# MotherBoard.net
KiCad netlist of a schematic drawn in EasyEDA Pro
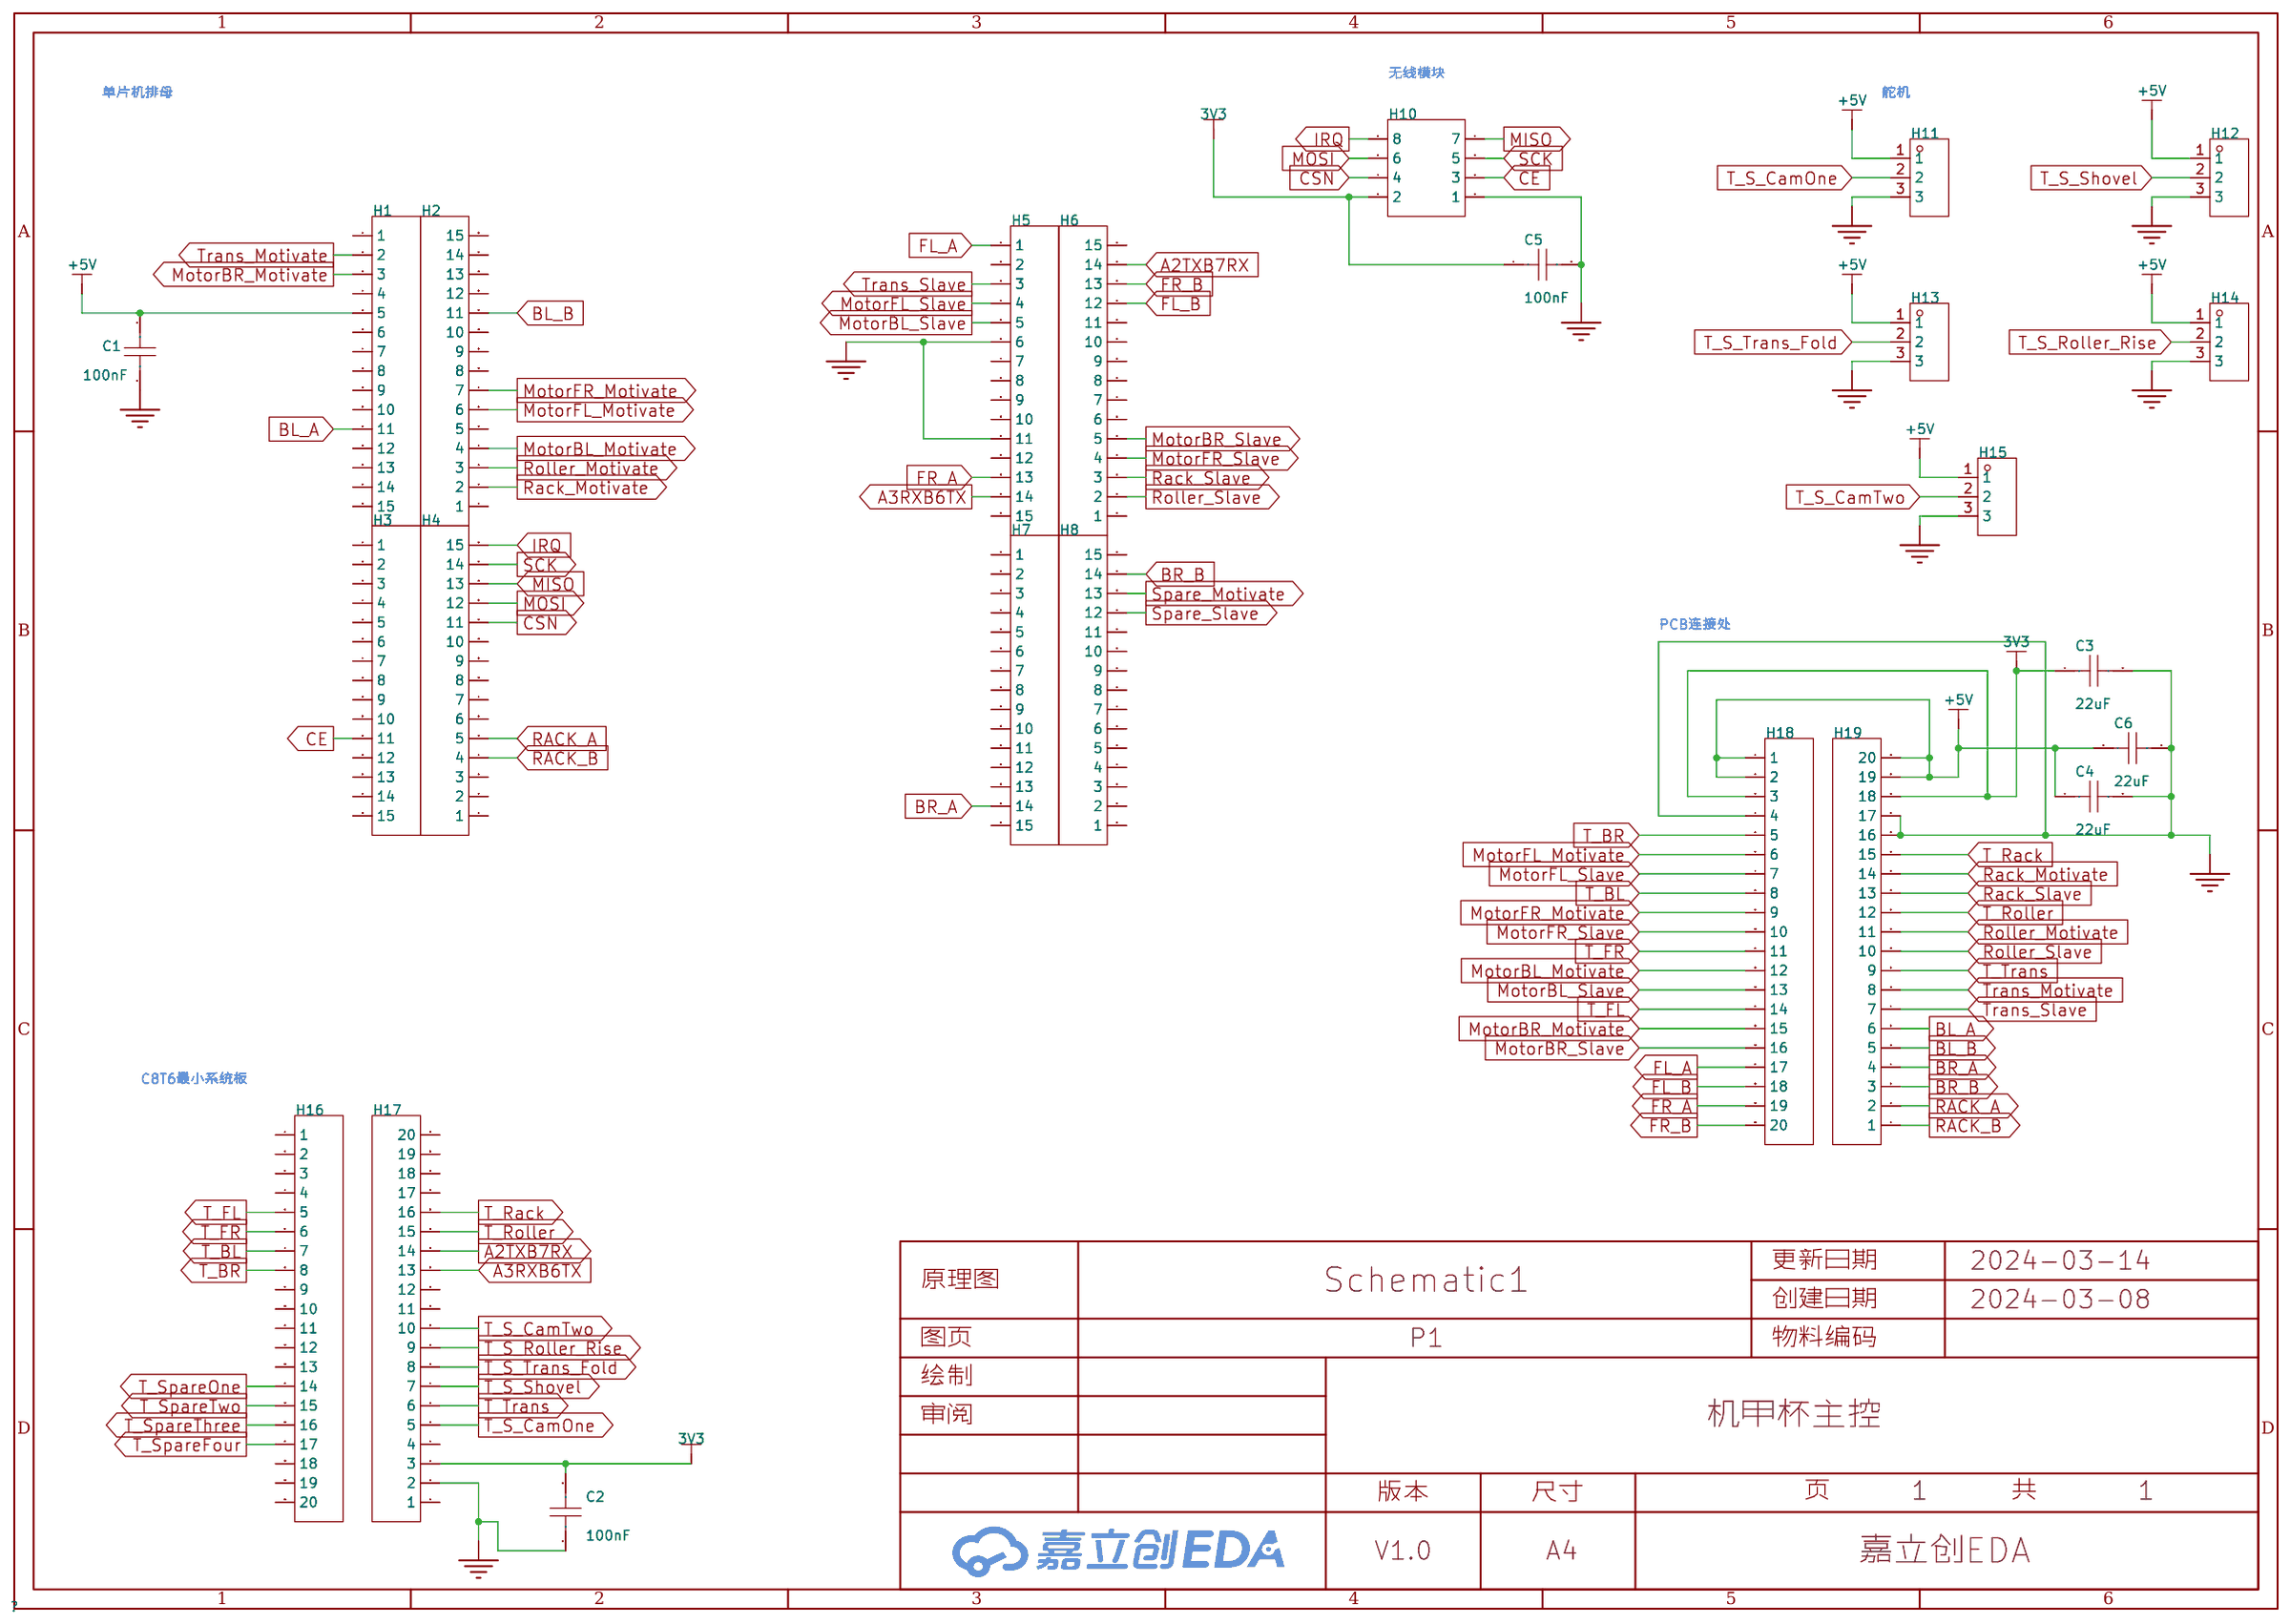
[diagram p0: schematic sheet]

(export (version "E")
  (design (tool "Eeschema 10.0.6"))
  (components
    (comp (ref "C1")
      (value "100nF")
      (footprint "easyedapro:C0603")
      (libsource (lib "easyedapro") (part "CapAcitance"))
    )
    (comp (ref "C2")
      (value "100nF")
      (footprint "easyedapro:C0603")
      (libsource (lib "easyedapro") (part "CapAcitance"))
    )
    (comp (ref "C3")
      (value "22uF")
      (footprint "easyedapro:C0603")
      (libsource (lib "easyedapro") (part "CapAcitance"))
    )
    (comp (ref "C4")
      (value "22uF")
      (footprint "easyedapro:C0603")
      (libsource (lib "easyedapro") (part "CapAcitance"))
    )
    (comp (ref "C5")
      (value "100nF")
      (footprint "easyedapro:C0603")
      (libsource (lib "easyedapro") (part "CapAcitance"))
    )
    (comp (ref "C6")
      (value "22uF")
      (footprint "easyedapro:C0603")
      (libsource (lib "easyedapro") (part "CapAcitance"))
    )
    (comp (ref "H1")
      (value "~")
      (footprint "easyedapro:HDR-TH_15P-P2.54-V-F-1")
      (libsource (lib "easyedapro") (part "HDR-F_2.54_1x15P"))
    )
    (comp (ref "H2")
      (value "~")
      (footprint "easyedapro:HDR-TH_15P-P2.54-V-F-1")
      (libsource (lib "easyedapro") (part "HDR-F_2.54_1x15P"))
    )
    (comp (ref "H3")
      (value "~")
      (footprint "easyedapro:HDR-TH_15P-P2.54-V-F-1")
      (libsource (lib "easyedapro") (part "HDR-F_2.54_1x15P"))
    )
    (comp (ref "H4")
      (value "~")
      (footprint "easyedapro:HDR-TH_15P-P2.54-V-F-1")
      (libsource (lib "easyedapro") (part "HDR-F_2.54_1x15P"))
    )
    (comp (ref "H5")
      (value "~")
      (footprint "easyedapro:HDR-TH_15P-P2.54-V-F-1")
      (libsource (lib "easyedapro") (part "HDR-F_2.54_1x15P"))
    )
    (comp (ref "H6")
      (value "~")
      (footprint "easyedapro:HDR-TH_15P-P2.54-V-F-1")
      (libsource (lib "easyedapro") (part "HDR-F_2.54_1x15P"))
    )
    (comp (ref "H7")
      (value "~")
      (footprint "easyedapro:HDR-TH_15P-P2.54-V-F-1")
      (libsource (lib "easyedapro") (part "HDR-F_2.54_1x15P"))
    )
    (comp (ref "H8")
      (value "~")
      (footprint "easyedapro:HDR-TH_15P-P2.54-V-F-1")
      (libsource (lib "easyedapro") (part "HDR-F_2.54_1x15P"))
    )
    (comp (ref "H10")
      (value "~")
      (footprint "easyedapro:HDR-TH_8P-P2.54-V-F-R2-C4-S2.54-1")
      (libsource (lib "easyedapro") (part "HDR-F-2.54_2x4"))
    )
    (comp (ref "H11")
      (value "~")
      (footprint "easyedapro:HDR-TH_3P-P2.54-V-M")
      (libsource (lib "easyedapro") (part "PZ254V-11-03P_C2937625"))
    )
    (comp (ref "H12")
      (value "~")
      (footprint "easyedapro:HDR-TH_3P-P2.54-V-M")
      (libsource (lib "easyedapro") (part "PZ254V-11-03P_C2937625"))
    )
    (comp (ref "H13")
      (value "~")
      (footprint "easyedapro:HDR-TH_3P-P2.54-V-M")
      (libsource (lib "easyedapro") (part "PZ254V-11-03P_C2937625"))
    )
    (comp (ref "H14")
      (value "~")
      (footprint "easyedapro:HDR-TH_3P-P2.54-V-M")
      (libsource (lib "easyedapro") (part "PZ254V-11-03P_C2937625"))
    )
    (comp (ref "H15")
      (value "~")
      (footprint "easyedapro:HDR-TH_3P-P2.54-V-M")
      (libsource (lib "easyedapro") (part "PZ254V-11-03P_C2937625"))
    )
    (comp (ref "H16")
      (value "~")
      (footprint "easyedapro:HDR-TH_20P-P2.54-V-F")
      (libsource (lib "easyedapro") (part "HDR-F_2.54_1x20P"))
    )
    (comp (ref "H17")
      (value "~")
      (footprint "easyedapro:HDR-TH_20P-P2.54-V-F")
      (libsource (lib "easyedapro") (part "HDR-F_2.54_1x20P"))
    )
    (comp (ref "H18")
      (value "~")
      (footprint "easyedapro:HDR-TH_20P-P2.54-V-F")
      (libsource (lib "easyedapro") (part "HDR-F_2.54_1x20P"))
    )
    (comp (ref "H19")
      (value "~")
      (footprint "easyedapro:HDR-TH_20P-P2.54-V-F")
      (libsource (lib "easyedapro") (part "HDR-F_2.54_1x20P"))
    )
  )
  (nets
    (net (code "1") (name "+5V") (class "Default")
      (node (ref "C1") (pin "2") (pinfunction "2_2") (pintype "input"))
      (node (ref "C4") (pin "1") (pinfunction "1_1") (pintype "input"))
      (node (ref "C6") (pin "2") (pinfunction "2_2") (pintype "input"))
      (node (ref "H1") (pin "5") (pinfunction "5_5") (pintype "input"))
      (node (ref "H11") (pin "1") (pinfunction "1_1") (pintype "input"))
      (node (ref "H12") (pin "1") (pinfunction "1_1") (pintype "input"))
      (node (ref "H13") (pin "1") (pinfunction "1_1") (pintype "input"))
      (node (ref "H14") (pin "1") (pinfunction "1_1") (pintype "input"))
      (node (ref "H15") (pin "1") (pinfunction "1_1") (pintype "input"))
      (node (ref "H18") (pin "1") (pinfunction "1_1") (pintype "input"))
      (node (ref "H18") (pin "2") (pinfunction "2_2") (pintype "input"))
      (node (ref "H19") (pin "19") (pinfunction "19_19") (pintype "input"))
      (node (ref "H19") (pin "20") (pinfunction "20_20") (pintype "input"))
    )
    (net (code "2") (name "3V3") (class "Default")
      (node (ref "C2") (pin "2") (pinfunction "2_2") (pintype "input"))
      (node (ref "C3") (pin "1") (pinfunction "1_1") (pintype "input"))
      (node (ref "C5") (pin "1") (pinfunction "1_1") (pintype "input"))
      (node (ref "H10") (pin "2") (pinfunction "2_2") (pintype "input"))
      (node (ref "H17") (pin "3") (pinfunction "3_3") (pintype "input"))
      (node (ref "H18") (pin "3") (pinfunction "3_3") (pintype "input"))
      (node (ref "H19") (pin "18") (pinfunction "18_18") (pintype "input"))
    )
    (net (code "3") (name "A2TXB7RX") (class "Default")
      (node (ref "H17") (pin "14") (pinfunction "14_14") (pintype "input"))
      (node (ref "H6") (pin "14") (pinfunction "14_14") (pintype "input"))
    )
    (net (code "4") (name "A3RXB6TX") (class "Default")
      (node (ref "H17") (pin "13") (pinfunction "13_13") (pintype "input"))
      (node (ref "H5") (pin "14") (pinfunction "14_14") (pintype "input"))
    )
    (net (code "5") (name "BL_A") (class "Default")
      (node (ref "H1") (pin "11") (pinfunction "11_11") (pintype "input"))
      (node (ref "H19") (pin "6") (pinfunction "6_6") (pintype "input"))
    )
    (net (code "6") (name "BL_B") (class "Default")
      (node (ref "H19") (pin "5") (pinfunction "5_5") (pintype "input"))
      (node (ref "H2") (pin "11") (pinfunction "11_11") (pintype "input"))
    )
    (net (code "7") (name "BR_A") (class "Default")
      (node (ref "H19") (pin "4") (pinfunction "4_4") (pintype "input"))
      (node (ref "H7") (pin "14") (pinfunction "14_14") (pintype "input"))
    )
    (net (code "8") (name "BR_B") (class "Default")
      (node (ref "H19") (pin "3") (pinfunction "3_3") (pintype "input"))
      (node (ref "H8") (pin "14") (pinfunction "14_14") (pintype "input"))
    )
    (net (code "9") (name "CE") (class "Default")
      (node (ref "H10") (pin "3") (pinfunction "3_3") (pintype "input"))
      (node (ref "H3") (pin "11") (pinfunction "11_11") (pintype "input"))
    )
    (net (code "10") (name "CSN") (class "Default")
      (node (ref "H10") (pin "4") (pinfunction "4_4") (pintype "input"))
      (node (ref "H4") (pin "11") (pinfunction "11_11") (pintype "input"))
    )
    (net (code "11") (name "FL_A") (class "Default")
      (node (ref "H18") (pin "17") (pinfunction "17_17") (pintype "input"))
      (node (ref "H5") (pin "1") (pinfunction "1_1") (pintype "input"))
    )
    (net (code "12") (name "FL_B") (class "Default")
      (node (ref "H18") (pin "18") (pinfunction "18_18") (pintype "input"))
      (node (ref "H6") (pin "12") (pinfunction "12_12") (pintype "input"))
    )
    (net (code "13") (name "FR_A") (class "Default")
      (node (ref "H18") (pin "19") (pinfunction "19_19") (pintype "input"))
      (node (ref "H5") (pin "13") (pinfunction "13_13") (pintype "input"))
    )
    (net (code "14") (name "FR_B") (class "Default")
      (node (ref "H18") (pin "20") (pinfunction "20_20") (pintype "input"))
      (node (ref "H6") (pin "13") (pinfunction "13_13") (pintype "input"))
    )
    (net (code "15") (name "GND") (class "Default")
      (node (ref "C1") (pin "1") (pinfunction "1_1") (pintype "input"))
      (node (ref "C2") (pin "1") (pinfunction "1_1") (pintype "input"))
      (node (ref "C3") (pin "2") (pinfunction "2_2") (pintype "input"))
      (node (ref "C4") (pin "2") (pinfunction "2_2") (pintype "input"))
      (node (ref "C5") (pin "2") (pinfunction "2_2") (pintype "input"))
      (node (ref "C6") (pin "1") (pinfunction "1_1") (pintype "input"))
      (node (ref "H10") (pin "1") (pinfunction "1_1") (pintype "input"))
      (node (ref "H11") (pin "3") (pinfunction "3_3") (pintype "input"))
      (node (ref "H12") (pin "3") (pinfunction "3_3") (pintype "input"))
      (node (ref "H13") (pin "3") (pinfunction "3_3") (pintype "input"))
      (node (ref "H14") (pin "3") (pinfunction "3_3") (pintype "input"))
      (node (ref "H15") (pin "3") (pinfunction "3_3") (pintype "input"))
      (node (ref "H17") (pin "2") (pinfunction "2_2") (pintype "input"))
      (node (ref "H18") (pin "4") (pinfunction "4_4") (pintype "input"))
      (node (ref "H19") (pin "16") (pinfunction "16_16") (pintype "input"))
      (node (ref "H19") (pin "17") (pinfunction "17_17") (pintype "input"))
      (node (ref "H5") (pin "11") (pinfunction "11_11") (pintype "input"))
      (node (ref "H5") (pin "6") (pinfunction "6_6") (pintype "input"))
    )
    (net (code "16") (name "IRQ") (class "Default")
      (node (ref "H10") (pin "8") (pinfunction "8_8") (pintype "input"))
      (node (ref "H4") (pin "15") (pinfunction "15_15") (pintype "input"))
    )
    (net (code "17") (name "MISO") (class "Default")
      (node (ref "H10") (pin "7") (pinfunction "7_7") (pintype "input"))
      (node (ref "H4") (pin "13") (pinfunction "13_13") (pintype "input"))
    )
    (net (code "18") (name "MOSI") (class "Default")
      (node (ref "H10") (pin "6") (pinfunction "6_6") (pintype "input"))
      (node (ref "H4") (pin "12") (pinfunction "12_12") (pintype "input"))
    )
    (net (code "19") (name "MotorBL_Motivate") (class "Default")
      (node (ref "H18") (pin "12") (pinfunction "12_12") (pintype "input"))
      (node (ref "H2") (pin "4") (pinfunction "4_4") (pintype "input"))
    )
    (net (code "20") (name "MotorBL_Slave") (class "Default")
      (node (ref "H18") (pin "13") (pinfunction "13_13") (pintype "input"))
      (node (ref "H5") (pin "5") (pinfunction "5_5") (pintype "input"))
    )
    (net (code "21") (name "MotorBR_Motivate") (class "Default")
      (node (ref "H1") (pin "3") (pinfunction "3_3") (pintype "input"))
      (node (ref "H18") (pin "15") (pinfunction "15_15") (pintype "input"))
    )
    (net (code "22") (name "MotorBR_Slave") (class "Default")
      (node (ref "H18") (pin "16") (pinfunction "16_16") (pintype "input"))
      (node (ref "H6") (pin "5") (pinfunction "5_5") (pintype "input"))
    )
    (net (code "23") (name "MotorFL_Motivate") (class "Default")
      (node (ref "H18") (pin "6") (pinfunction "6_6") (pintype "input"))
      (node (ref "H2") (pin "6") (pinfunction "6_6") (pintype "input"))
    )
    (net (code "24") (name "MotorFL_Slave") (class "Default")
      (node (ref "H18") (pin "7") (pinfunction "7_7") (pintype "input"))
      (node (ref "H5") (pin "4") (pinfunction "4_4") (pintype "input"))
    )
    (net (code "25") (name "MotorFR_Motivate") (class "Default")
      (node (ref "H18") (pin "9") (pinfunction "9_9") (pintype "input"))
      (node (ref "H2") (pin "7") (pinfunction "7_7") (pintype "input"))
    )
    (net (code "26") (name "MotorFR_Slave") (class "Default")
      (node (ref "H18") (pin "10") (pinfunction "10_10") (pintype "input"))
      (node (ref "H6") (pin "4") (pinfunction "4_4") (pintype "input"))
    )
    (net (code "27") (name "RACK_A") (class "Default")
      (node (ref "H19") (pin "2") (pinfunction "2_2") (pintype "input"))
      (node (ref "H4") (pin "5") (pinfunction "5_5") (pintype "input"))
    )
    (net (code "28") (name "RACK_B") (class "Default")
      (node (ref "H19") (pin "1") (pinfunction "1_1") (pintype "input"))
      (node (ref "H4") (pin "4") (pinfunction "4_4") (pintype "input"))
    )
    (net (code "29") (name "Rack_Motivate") (class "Default")
      (node (ref "H19") (pin "14") (pinfunction "14_14") (pintype "input"))
      (node (ref "H2") (pin "2") (pinfunction "2_2") (pintype "input"))
    )
    (net (code "30") (name "Rack_Slave") (class "Default")
      (node (ref "H19") (pin "13") (pinfunction "13_13") (pintype "input"))
      (node (ref "H6") (pin "3") (pinfunction "3_3") (pintype "input"))
    )
    (net (code "31") (name "Roller_Motivate") (class "Default")
      (node (ref "H19") (pin "11") (pinfunction "11_11") (pintype "input"))
      (node (ref "H2") (pin "3") (pinfunction "3_3") (pintype "input"))
    )
    (net (code "32") (name "Roller_Slave") (class "Default")
      (node (ref "H19") (pin "10") (pinfunction "10_10") (pintype "input"))
      (node (ref "H6") (pin "2") (pinfunction "2_2") (pintype "input"))
    )
    (net (code "33") (name "SCK") (class "Default")
      (node (ref "H10") (pin "5") (pinfunction "5_5") (pintype "input"))
      (node (ref "H4") (pin "14") (pinfunction "14_14") (pintype "input"))
    )
    (net (code "34") (name "Spare_Motivate") (class "Default")
      (node (ref "H8") (pin "13") (pinfunction "13_13") (pintype "input"))
    )
    (net (code "35") (name "Spare_Slave") (class "Default")
      (node (ref "H8") (pin "12") (pinfunction "12_12") (pintype "input"))
    )
    (net (code "36") (name "T_BL") (class "Default")
      (node (ref "H16") (pin "7") (pinfunction "7_7") (pintype "input"))
      (node (ref "H18") (pin "8") (pinfunction "8_8") (pintype "input"))
    )
    (net (code "37") (name "T_BR") (class "Default")
      (node (ref "H16") (pin "8") (pinfunction "8_8") (pintype "input"))
      (node (ref "H18") (pin "5") (pinfunction "5_5") (pintype "input"))
    )
    (net (code "38") (name "T_FL") (class "Default")
      (node (ref "H16") (pin "5") (pinfunction "5_5") (pintype "input"))
      (node (ref "H18") (pin "14") (pinfunction "14_14") (pintype "input"))
    )
    (net (code "39") (name "T_FR") (class "Default")
      (node (ref "H16") (pin "6") (pinfunction "6_6") (pintype "input"))
      (node (ref "H18") (pin "11") (pinfunction "11_11") (pintype "input"))
    )
    (net (code "40") (name "T_Rack") (class "Default")
      (node (ref "H17") (pin "16") (pinfunction "16_16") (pintype "input"))
      (node (ref "H19") (pin "15") (pinfunction "15_15") (pintype "input"))
    )
    (net (code "41") (name "T_Roller") (class "Default")
      (node (ref "H17") (pin "15") (pinfunction "15_15") (pintype "input"))
      (node (ref "H19") (pin "12") (pinfunction "12_12") (pintype "input"))
    )
    (net (code "42") (name "T_S_CamOne") (class "Default")
      (node (ref "H11") (pin "2") (pinfunction "2_2") (pintype "input"))
      (node (ref "H17") (pin "5") (pinfunction "5_5") (pintype "input"))
    )
    (net (code "43") (name "T_S_CamTwo") (class "Default")
      (node (ref "H15") (pin "2") (pinfunction "2_2") (pintype "input"))
      (node (ref "H17") (pin "10") (pinfunction "10_10") (pintype "input"))
    )
    (net (code "44") (name "T_S_Roller_Rise") (class "Default")
      (node (ref "H14") (pin "2") (pinfunction "2_2") (pintype "input"))
      (node (ref "H17") (pin "9") (pinfunction "9_9") (pintype "input"))
    )
    (net (code "45") (name "T_S_Shovel") (class "Default")
      (node (ref "H12") (pin "2") (pinfunction "2_2") (pintype "input"))
      (node (ref "H17") (pin "7") (pinfunction "7_7") (pintype "input"))
    )
    (net (code "46") (name "T_S_Trans_Fold") (class "Default")
      (node (ref "H13") (pin "2") (pinfunction "2_2") (pintype "input"))
      (node (ref "H17") (pin "8") (pinfunction "8_8") (pintype "input"))
    )
    (net (code "47") (name "T_SpareFour") (class "Default")
      (node (ref "H16") (pin "17") (pinfunction "17_17") (pintype "input"))
    )
    (net (code "48") (name "T_SpareOne") (class "Default")
      (node (ref "H16") (pin "14") (pinfunction "14_14") (pintype "input"))
    )
    (net (code "49") (name "T_SpareThree") (class "Default")
      (node (ref "H16") (pin "16") (pinfunction "16_16") (pintype "input"))
    )
    (net (code "50") (name "T_SpareTwo") (class "Default")
      (node (ref "H16") (pin "15") (pinfunction "15_15") (pintype "input"))
    )
    (net (code "51") (name "T_Trans") (class "Default")
      (node (ref "H17") (pin "6") (pinfunction "6_6") (pintype "input"))
      (node (ref "H19") (pin "9") (pinfunction "9_9") (pintype "input"))
    )
    (net (code "52") (name "Trans_Motivate") (class "Default")
      (node (ref "H1") (pin "2") (pinfunction "2_2") (pintype "input"))
      (node (ref "H19") (pin "8") (pinfunction "8_8") (pintype "input"))
    )
    (net (code "53") (name "Trans_Slave") (class "Default")
      (node (ref "H19") (pin "7") (pinfunction "7_7") (pintype "input"))
      (node (ref "H5") (pin "3") (pinfunction "3_3") (pintype "input"))
    )
    (net (code "54") (name "unconnected-(H1-Pad1)") (class "Default")
      (node (ref "H1") (pin "1") (pinfunction "1_1") (pintype "input"))
    )
    (net (code "55") (name "unconnected-(H1-Pad4)") (class "Default")
      (node (ref "H1") (pin "4") (pinfunction "4_4") (pintype "input"))
    )
    (net (code "56") (name "unconnected-(H1-Pad6)") (class "Default")
      (node (ref "H1") (pin "6") (pinfunction "6_6") (pintype "input"))
    )
    (net (code "57") (name "unconnected-(H1-Pad7)") (class "Default")
      (node (ref "H1") (pin "7") (pinfunction "7_7") (pintype "input"))
    )
    (net (code "58") (name "unconnected-(H1-Pad8)") (class "Default")
      (node (ref "H1") (pin "8") (pinfunction "8_8") (pintype "input"))
    )
    (net (code "59") (name "unconnected-(H1-Pad9)") (class "Default")
      (node (ref "H1") (pin "9") (pinfunction "9_9") (pintype "input"))
    )
    (net (code "60") (name "unconnected-(H1-Pad10)") (class "Default")
      (node (ref "H1") (pin "10") (pinfunction "10_10") (pintype "input"))
    )
    (net (code "61") (name "unconnected-(H1-Pad12)") (class "Default")
      (node (ref "H1") (pin "12") (pinfunction "12_12") (pintype "input"))
    )
    (net (code "62") (name "unconnected-(H1-Pad13)") (class "Default")
      (node (ref "H1") (pin "13") (pinfunction "13_13") (pintype "input"))
    )
    (net (code "63") (name "unconnected-(H1-Pad14)") (class "Default")
      (node (ref "H1") (pin "14") (pinfunction "14_14") (pintype "input"))
    )
    (net (code "64") (name "unconnected-(H1-Pad15)") (class "Default")
      (node (ref "H1") (pin "15") (pinfunction "15_15") (pintype "input"))
    )
    (net (code "65") (name "unconnected-(H2-Pad1)") (class "Default")
      (node (ref "H2") (pin "1") (pinfunction "1_1") (pintype "input"))
    )
    (net (code "66") (name "unconnected-(H2-Pad5)") (class "Default")
      (node (ref "H2") (pin "5") (pinfunction "5_5") (pintype "input"))
    )
    (net (code "67") (name "unconnected-(H2-Pad8)") (class "Default")
      (node (ref "H2") (pin "8") (pinfunction "8_8") (pintype "input"))
    )
    (net (code "68") (name "unconnected-(H2-Pad9)") (class "Default")
      (node (ref "H2") (pin "9") (pinfunction "9_9") (pintype "input"))
    )
    (net (code "69") (name "unconnected-(H2-Pad10)") (class "Default")
      (node (ref "H2") (pin "10") (pinfunction "10_10") (pintype "input"))
    )
    (net (code "70") (name "unconnected-(H2-Pad12)") (class "Default")
      (node (ref "H2") (pin "12") (pinfunction "12_12") (pintype "input"))
    )
    (net (code "71") (name "unconnected-(H2-Pad13)") (class "Default")
      (node (ref "H2") (pin "13") (pinfunction "13_13") (pintype "input"))
    )
    (net (code "72") (name "unconnected-(H2-Pad14)") (class "Default")
      (node (ref "H2") (pin "14") (pinfunction "14_14") (pintype "input"))
    )
    (net (code "73") (name "unconnected-(H2-Pad15)") (class "Default")
      (node (ref "H2") (pin "15") (pinfunction "15_15") (pintype "input"))
    )
    (net (code "74") (name "unconnected-(H3-Pad1)") (class "Default")
      (node (ref "H3") (pin "1") (pinfunction "1_1") (pintype "input"))
    )
    (net (code "75") (name "unconnected-(H3-Pad2)") (class "Default")
      (node (ref "H3") (pin "2") (pinfunction "2_2") (pintype "input"))
    )
    (net (code "76") (name "unconnected-(H3-Pad3)") (class "Default")
      (node (ref "H3") (pin "3") (pinfunction "3_3") (pintype "input"))
    )
    (net (code "77") (name "unconnected-(H3-Pad4)") (class "Default")
      (node (ref "H3") (pin "4") (pinfunction "4_4") (pintype "input"))
    )
    (net (code "78") (name "unconnected-(H3-Pad5)") (class "Default")
      (node (ref "H3") (pin "5") (pinfunction "5_5") (pintype "input"))
    )
    (net (code "79") (name "unconnected-(H3-Pad6)") (class "Default")
      (node (ref "H3") (pin "6") (pinfunction "6_6") (pintype "input"))
    )
    (net (code "80") (name "unconnected-(H3-Pad7)") (class "Default")
      (node (ref "H3") (pin "7") (pinfunction "7_7") (pintype "input"))
    )
    (net (code "81") (name "unconnected-(H3-Pad8)") (class "Default")
      (node (ref "H3") (pin "8") (pinfunction "8_8") (pintype "input"))
    )
    (net (code "82") (name "unconnected-(H3-Pad9)") (class "Default")
      (node (ref "H3") (pin "9") (pinfunction "9_9") (pintype "input"))
    )
    (net (code "83") (name "unconnected-(H3-Pad10)") (class "Default")
      (node (ref "H3") (pin "10") (pinfunction "10_10") (pintype "input"))
    )
    (net (code "84") (name "unconnected-(H3-Pad12)") (class "Default")
      (node (ref "H3") (pin "12") (pinfunction "12_12") (pintype "input"))
    )
    (net (code "85") (name "unconnected-(H3-Pad13)") (class "Default")
      (node (ref "H3") (pin "13") (pinfunction "13_13") (pintype "input"))
    )
    (net (code "86") (name "unconnected-(H3-Pad14)") (class "Default")
      (node (ref "H3") (pin "14") (pinfunction "14_14") (pintype "input"))
    )
    (net (code "87") (name "unconnected-(H3-Pad15)") (class "Default")
      (node (ref "H3") (pin "15") (pinfunction "15_15") (pintype "input"))
    )
    (net (code "88") (name "unconnected-(H4-Pad1)") (class "Default")
      (node (ref "H4") (pin "1") (pinfunction "1_1") (pintype "input"))
    )
    (net (code "89") (name "unconnected-(H4-Pad2)") (class "Default")
      (node (ref "H4") (pin "2") (pinfunction "2_2") (pintype "input"))
    )
    (net (code "90") (name "unconnected-(H4-Pad3)") (class "Default")
      (node (ref "H4") (pin "3") (pinfunction "3_3") (pintype "input"))
    )
    (net (code "91") (name "unconnected-(H4-Pad6)") (class "Default")
      (node (ref "H4") (pin "6") (pinfunction "6_6") (pintype "input"))
    )
    (net (code "92") (name "unconnected-(H4-Pad7)") (class "Default")
      (node (ref "H4") (pin "7") (pinfunction "7_7") (pintype "input"))
    )
    (net (code "93") (name "unconnected-(H4-Pad8)") (class "Default")
      (node (ref "H4") (pin "8") (pinfunction "8_8") (pintype "input"))
    )
    (net (code "94") (name "unconnected-(H4-Pad9)") (class "Default")
      (node (ref "H4") (pin "9") (pinfunction "9_9") (pintype "input"))
    )
    (net (code "95") (name "unconnected-(H4-Pad10)") (class "Default")
      (node (ref "H4") (pin "10") (pinfunction "10_10") (pintype "input"))
    )
    (net (code "96") (name "unconnected-(H5-Pad2)") (class "Default")
      (node (ref "H5") (pin "2") (pinfunction "2_2") (pintype "input"))
    )
    (net (code "97") (name "unconnected-(H5-Pad7)") (class "Default")
      (node (ref "H5") (pin "7") (pinfunction "7_7") (pintype "input"))
    )
    (net (code "98") (name "unconnected-(H5-Pad8)") (class "Default")
      (node (ref "H5") (pin "8") (pinfunction "8_8") (pintype "input"))
    )
    (net (code "99") (name "unconnected-(H5-Pad9)") (class "Default")
      (node (ref "H5") (pin "9") (pinfunction "9_9") (pintype "input"))
    )
    (net (code "100") (name "unconnected-(H5-Pad10)") (class "Default")
      (node (ref "H5") (pin "10") (pinfunction "10_10") (pintype "input"))
    )
    (net (code "101") (name "unconnected-(H5-Pad12)") (class "Default")
      (node (ref "H5") (pin "12") (pinfunction "12_12") (pintype "input"))
    )
    (net (code "102") (name "unconnected-(H5-Pad15)") (class "Default")
      (node (ref "H5") (pin "15") (pinfunction "15_15") (pintype "input"))
    )
    (net (code "103") (name "unconnected-(H6-Pad1)") (class "Default")
      (node (ref "H6") (pin "1") (pinfunction "1_1") (pintype "input"))
    )
    (net (code "104") (name "unconnected-(H6-Pad6)") (class "Default")
      (node (ref "H6") (pin "6") (pinfunction "6_6") (pintype "input"))
    )
    (net (code "105") (name "unconnected-(H6-Pad7)") (class "Default")
      (node (ref "H6") (pin "7") (pinfunction "7_7") (pintype "input"))
    )
    (net (code "106") (name "unconnected-(H6-Pad8)") (class "Default")
      (node (ref "H6") (pin "8") (pinfunction "8_8") (pintype "input"))
    )
    (net (code "107") (name "unconnected-(H6-Pad9)") (class "Default")
      (node (ref "H6") (pin "9") (pinfunction "9_9") (pintype "input"))
    )
    (net (code "108") (name "unconnected-(H6-Pad10)") (class "Default")
      (node (ref "H6") (pin "10") (pinfunction "10_10") (pintype "input"))
    )
    (net (code "109") (name "unconnected-(H6-Pad11)") (class "Default")
      (node (ref "H6") (pin "11") (pinfunction "11_11") (pintype "input"))
    )
    (net (code "110") (name "unconnected-(H6-Pad15)") (class "Default")
      (node (ref "H6") (pin "15") (pinfunction "15_15") (pintype "input"))
    )
    (net (code "111") (name "unconnected-(H7-Pad1)") (class "Default")
      (node (ref "H7") (pin "1") (pinfunction "1_1") (pintype "input"))
    )
    (net (code "112") (name "unconnected-(H7-Pad2)") (class "Default")
      (node (ref "H7") (pin "2") (pinfunction "2_2") (pintype "input"))
    )
    (net (code "113") (name "unconnected-(H7-Pad3)") (class "Default")
      (node (ref "H7") (pin "3") (pinfunction "3_3") (pintype "input"))
    )
    (net (code "114") (name "unconnected-(H7-Pad4)") (class "Default")
      (node (ref "H7") (pin "4") (pinfunction "4_4") (pintype "input"))
    )
    (net (code "115") (name "unconnected-(H7-Pad5)") (class "Default")
      (node (ref "H7") (pin "5") (pinfunction "5_5") (pintype "input"))
    )
    (net (code "116") (name "unconnected-(H7-Pad6)") (class "Default")
      (node (ref "H7") (pin "6") (pinfunction "6_6") (pintype "input"))
    )
    (net (code "117") (name "unconnected-(H7-Pad7)") (class "Default")
      (node (ref "H7") (pin "7") (pinfunction "7_7") (pintype "input"))
    )
    (net (code "118") (name "unconnected-(H7-Pad8)") (class "Default")
      (node (ref "H7") (pin "8") (pinfunction "8_8") (pintype "input"))
    )
    (net (code "119") (name "unconnected-(H7-Pad9)") (class "Default")
      (node (ref "H7") (pin "9") (pinfunction "9_9") (pintype "input"))
    )
    (net (code "120") (name "unconnected-(H7-Pad10)") (class "Default")
      (node (ref "H7") (pin "10") (pinfunction "10_10") (pintype "input"))
    )
    (net (code "121") (name "unconnected-(H7-Pad11)") (class "Default")
      (node (ref "H7") (pin "11") (pinfunction "11_11") (pintype "input"))
    )
    (net (code "122") (name "unconnected-(H7-Pad12)") (class "Default")
      (node (ref "H7") (pin "12") (pinfunction "12_12") (pintype "input"))
    )
    (net (code "123") (name "unconnected-(H7-Pad13)") (class "Default")
      (node (ref "H7") (pin "13") (pinfunction "13_13") (pintype "input"))
    )
    (net (code "124") (name "unconnected-(H7-Pad15)") (class "Default")
      (node (ref "H7") (pin "15") (pinfunction "15_15") (pintype "input"))
    )
    (net (code "125") (name "unconnected-(H8-Pad1)") (class "Default")
      (node (ref "H8") (pin "1") (pinfunction "1_1") (pintype "input"))
    )
    (net (code "126") (name "unconnected-(H8-Pad2)") (class "Default")
      (node (ref "H8") (pin "2") (pinfunction "2_2") (pintype "input"))
    )
    (net (code "127") (name "unconnected-(H8-Pad3)") (class "Default")
      (node (ref "H8") (pin "3") (pinfunction "3_3") (pintype "input"))
    )
    (net (code "128") (name "unconnected-(H8-Pad4)") (class "Default")
      (node (ref "H8") (pin "4") (pinfunction "4_4") (pintype "input"))
    )
    (net (code "129") (name "unconnected-(H8-Pad5)") (class "Default")
      (node (ref "H8") (pin "5") (pinfunction "5_5") (pintype "input"))
    )
    (net (code "130") (name "unconnected-(H8-Pad6)") (class "Default")
      (node (ref "H8") (pin "6") (pinfunction "6_6") (pintype "input"))
    )
    (net (code "131") (name "unconnected-(H8-Pad7)") (class "Default")
      (node (ref "H8") (pin "7") (pinfunction "7_7") (pintype "input"))
    )
    (net (code "132") (name "unconnected-(H8-Pad8)") (class "Default")
      (node (ref "H8") (pin "8") (pinfunction "8_8") (pintype "input"))
    )
    (net (code "133") (name "unconnected-(H8-Pad9)") (class "Default")
      (node (ref "H8") (pin "9") (pinfunction "9_9") (pintype "input"))
    )
    (net (code "134") (name "unconnected-(H8-Pad10)") (class "Default")
      (node (ref "H8") (pin "10") (pinfunction "10_10") (pintype "input"))
    )
    (net (code "135") (name "unconnected-(H8-Pad11)") (class "Default")
      (node (ref "H8") (pin "11") (pinfunction "11_11") (pintype "input"))
    )
    (net (code "136") (name "unconnected-(H8-Pad15)") (class "Default")
      (node (ref "H8") (pin "15") (pinfunction "15_15") (pintype "input"))
    )
    (net (code "137") (name "unconnected-(H16-Pad1)") (class "Default")
      (node (ref "H16") (pin "1") (pinfunction "1_1") (pintype "input"))
    )
    (net (code "138") (name "unconnected-(H16-Pad2)") (class "Default")
      (node (ref "H16") (pin "2") (pinfunction "2_2") (pintype "input"))
    )
    (net (code "139") (name "unconnected-(H16-Pad3)") (class "Default")
      (node (ref "H16") (pin "3") (pinfunction "3_3") (pintype "input"))
    )
    (net (code "140") (name "unconnected-(H16-Pad4)") (class "Default")
      (node (ref "H16") (pin "4") (pinfunction "4_4") (pintype "input"))
    )
    (net (code "141") (name "unconnected-(H16-Pad9)") (class "Default")
      (node (ref "H16") (pin "9") (pinfunction "9_9") (pintype "input"))
    )
    (net (code "142") (name "unconnected-(H16-Pad10)") (class "Default")
      (node (ref "H16") (pin "10") (pinfunction "10_10") (pintype "input"))
    )
    (net (code "143") (name "unconnected-(H16-Pad11)") (class "Default")
      (node (ref "H16") (pin "11") (pinfunction "11_11") (pintype "input"))
    )
    (net (code "144") (name "unconnected-(H16-Pad12)") (class "Default")
      (node (ref "H16") (pin "12") (pinfunction "12_12") (pintype "input"))
    )
    (net (code "145") (name "unconnected-(H16-Pad13)") (class "Default")
      (node (ref "H16") (pin "13") (pinfunction "13_13") (pintype "input"))
    )
    (net (code "146") (name "unconnected-(H16-Pad18)") (class "Default")
      (node (ref "H16") (pin "18") (pinfunction "18_18") (pintype "input"))
    )
    (net (code "147") (name "unconnected-(H16-Pad19)") (class "Default")
      (node (ref "H16") (pin "19") (pinfunction "19_19") (pintype "input"))
    )
    (net (code "148") (name "unconnected-(H16-Pad20)") (class "Default")
      (node (ref "H16") (pin "20") (pinfunction "20_20") (pintype "input"))
    )
    (net (code "149") (name "unconnected-(H17-Pad1)") (class "Default")
      (node (ref "H17") (pin "1") (pinfunction "1_1") (pintype "input"))
    )
    (net (code "150") (name "unconnected-(H17-Pad4)") (class "Default")
      (node (ref "H17") (pin "4") (pinfunction "4_4") (pintype "input"))
    )
    (net (code "151") (name "unconnected-(H17-Pad11)") (class "Default")
      (node (ref "H17") (pin "11") (pinfunction "11_11") (pintype "input"))
    )
    (net (code "152") (name "unconnected-(H17-Pad12)") (class "Default")
      (node (ref "H17") (pin "12") (pinfunction "12_12") (pintype "input"))
    )
    (net (code "153") (name "unconnected-(H17-Pad17)") (class "Default")
      (node (ref "H17") (pin "17") (pinfunction "17_17") (pintype "input"))
    )
    (net (code "154") (name "unconnected-(H17-Pad18)") (class "Default")
      (node (ref "H17") (pin "18") (pinfunction "18_18") (pintype "input"))
    )
    (net (code "155") (name "unconnected-(H17-Pad19)") (class "Default")
      (node (ref "H17") (pin "19") (pinfunction "19_19") (pintype "input"))
    )
    (net (code "156") (name "unconnected-(H17-Pad20)") (class "Default")
      (node (ref "H17") (pin "20") (pinfunction "20_20") (pintype "input"))
    )
  )
)
